# Power.net
KiCad netlist of a schematic drawn in Altium Designer
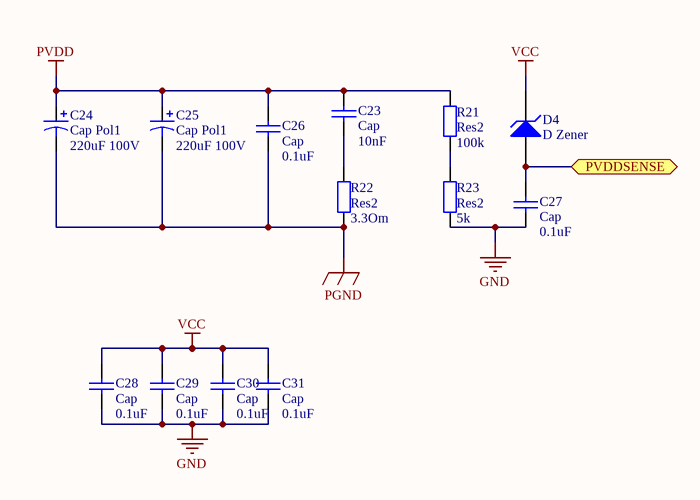
[diagram p0: Power.SchDoc]

(export (version "E")
  (design (tool "Eeschema 10.0.6"))
  (components
    (comp (ref "C23")
      (value "Cap")
      (footprint "6-0805_N")
      (description "Capacitor")
      (fields (field (name "ALTIUM_VALUE") "10nF") (field (name "PUBLISHER") "Altium Limited"))
      (libsource (lib "Miscellaneous Devices") (part "Cap"))
    )
    (comp (ref "C24")
      (value "Cap Pol1")
      (footprint "RB7.6-15")
      (description "Polarized Capacitor (Radial)")
      (fields (field (name "ALTIUM_VALUE") "220uF 100V") (field (name "PUBLISHER") "Altium Limited"))
      (libsource (lib "Miscellaneous Devices") (part "Cap Pol1"))
    )
    (comp (ref "C25")
      (value "Cap Pol1")
      (footprint "RB7.6-15")
      (description "Polarized Capacitor (Radial)")
      (fields (field (name "ALTIUM_VALUE") "220uF 100V") (field (name "PUBLISHER") "Altium Limited"))
      (libsource (lib "Miscellaneous Devices") (part "Cap Pol1"))
    )
    (comp (ref "C26")
      (value "Cap")
      (footprint "6-0805_N")
      (description "Capacitor")
      (fields (field (name "ALTIUM_VALUE") "0.1uF") (field (name "PUBLISHER") "Altium Limited"))
      (libsource (lib "Miscellaneous Devices") (part "Cap"))
    )
    (comp (ref "C27")
      (value "Cap")
      (footprint "6-0805_N")
      (description "Capacitor")
      (fields (field (name "ALTIUM_VALUE") "0.1uF") (field (name "PUBLISHER") "Altium Limited"))
      (libsource (lib "Miscellaneous Devices") (part "Cap"))
    )
    (comp (ref "C28")
      (value "Cap")
      (footprint "6-0805_N")
      (description "Capacitor")
      (fields (field (name "ALTIUM_VALUE") "0.1uF") (field (name "PUBLISHER") "Altium Limited"))
      (libsource (lib "Miscellaneous Devices") (part "Cap"))
    )
    (comp (ref "C29")
      (value "Cap")
      (footprint "6-0805_N")
      (description "Capacitor")
      (fields (field (name "ALTIUM_VALUE") "0.1uF") (field (name "PUBLISHER") "Altium Limited"))
      (libsource (lib "Miscellaneous Devices") (part "Cap"))
    )
    (comp (ref "C30")
      (value "Cap")
      (footprint "6-0805_N")
      (description "Capacitor")
      (fields (field (name "ALTIUM_VALUE") "0.1uF") (field (name "PUBLISHER") "Altium Limited"))
      (libsource (lib "Miscellaneous Devices") (part "Cap"))
    )
    (comp (ref "C31")
      (value "Cap")
      (footprint "6-0805_N")
      (description "Capacitor")
      (fields (field (name "ALTIUM_VALUE") "0.1uF") (field (name "PUBLISHER") "Altium Limited"))
      (libsource (lib "Miscellaneous Devices") (part "Cap"))
    )
    (comp (ref "D4")
      (value "D Zener")
      (footprint "SMB")
      (description "Zener Diode")
      (fields (field (name "PUBLISHER") "Altium Limited"))
      (libsource (lib "Miscellaneous Devices") (part "D Zener"))
    )
    (comp (ref "R21")
      (value "Res2")
      (footprint "6-0805_N")
      (description "Resistor")
      (fields (field (name "ALTIUM_VALUE") "100k") (field (name "PUBLISHER") "Altium Limited"))
      (libsource (lib "Miscellaneous Devices") (part "Res2"))
    )
    (comp (ref "R22")
      (value "Res2")
      (footprint "6-0805_N")
      (description "Resistor")
      (fields (field (name "ALTIUM_VALUE") "3.3Om") (field (name "PUBLISHER") "Altium Limited"))
      (libsource (lib "Miscellaneous Devices") (part "Res2"))
    )
    (comp (ref "R23")
      (value "Res2")
      (footprint "6-0805_N")
      (description "Resistor")
      (fields (field (name "ALTIUM_VALUE") "5k") (field (name "PUBLISHER") "Altium Limited"))
      (libsource (lib "Miscellaneous Devices") (part "Res2"))
    )
  )
  (nets
    (net (code "1") (name "/PVDDSENSE") (class "Default")
      (node (ref "C27") (pin "2") (pinfunction "2_2") (pintype "passive"))
      (node (ref "D4") (pin "1") (pinfunction "A_1") (pintype "passive"))
    )
    (net (code "2") (name "GND") (class "Default")
      (node (ref "C27") (pin "1") (pinfunction "1_1") (pintype "passive"))
      (node (ref "C28") (pin "1") (pinfunction "1_1") (pintype "passive"))
      (node (ref "C29") (pin "1") (pinfunction "1_1") (pintype "passive"))
      (node (ref "C30") (pin "1") (pinfunction "1_1") (pintype "passive"))
      (node (ref "C31") (pin "1") (pinfunction "1_1") (pintype "passive"))
      (node (ref "R23") (pin "2") (pinfunction "2_2") (pintype "passive"))
    )
    (net (code "3") (name "Net-(C23-Pad1)") (class "Default")
      (node (ref "C23") (pin "1") (pinfunction "1_1") (pintype "passive"))
      (node (ref "R22") (pin "1") (pinfunction "1_1") (pintype "passive"))
    )
    (net (code "4") (name "Net-(R21-Pad2)") (class "Default")
      (node (ref "R21") (pin "2") (pinfunction "2_2") (pintype "passive"))
      (node (ref "R23") (pin "1") (pinfunction "1_1") (pintype "passive"))
    )
    (net (code "5") (name "PGND") (class "Default")
      (node (ref "C24") (pin "2") (pinfunction "2_2") (pintype "passive"))
      (node (ref "C25") (pin "2") (pinfunction "2_2") (pintype "passive"))
      (node (ref "C26") (pin "1") (pinfunction "1_1") (pintype "passive"))
      (node (ref "R22") (pin "2") (pinfunction "2_2") (pintype "passive"))
    )
    (net (code "6") (name "PVDD") (class "Default")
      (node (ref "C23") (pin "2") (pinfunction "2_2") (pintype "passive"))
      (node (ref "C24") (pin "1") (pinfunction "1_1") (pintype "passive"))
      (node (ref "C25") (pin "1") (pinfunction "1_1") (pintype "passive"))
      (node (ref "C26") (pin "2") (pinfunction "2_2") (pintype "passive"))
      (node (ref "R21") (pin "1") (pinfunction "1_1") (pintype "passive"))
    )
    (net (code "7") (name "VCC") (class "Default")
      (node (ref "C28") (pin "2") (pinfunction "2_2") (pintype "passive"))
      (node (ref "C29") (pin "2") (pinfunction "2_2") (pintype "passive"))
      (node (ref "C30") (pin "2") (pinfunction "2_2") (pintype "passive"))
      (node (ref "C31") (pin "2") (pinfunction "2_2") (pintype "passive"))
      (node (ref "D4") (pin "2") (pinfunction "K_2") (pintype "passive"))
    )
  )
)
